# Sensors.net
KiCad netlist of a schematic drawn in Altium Designer
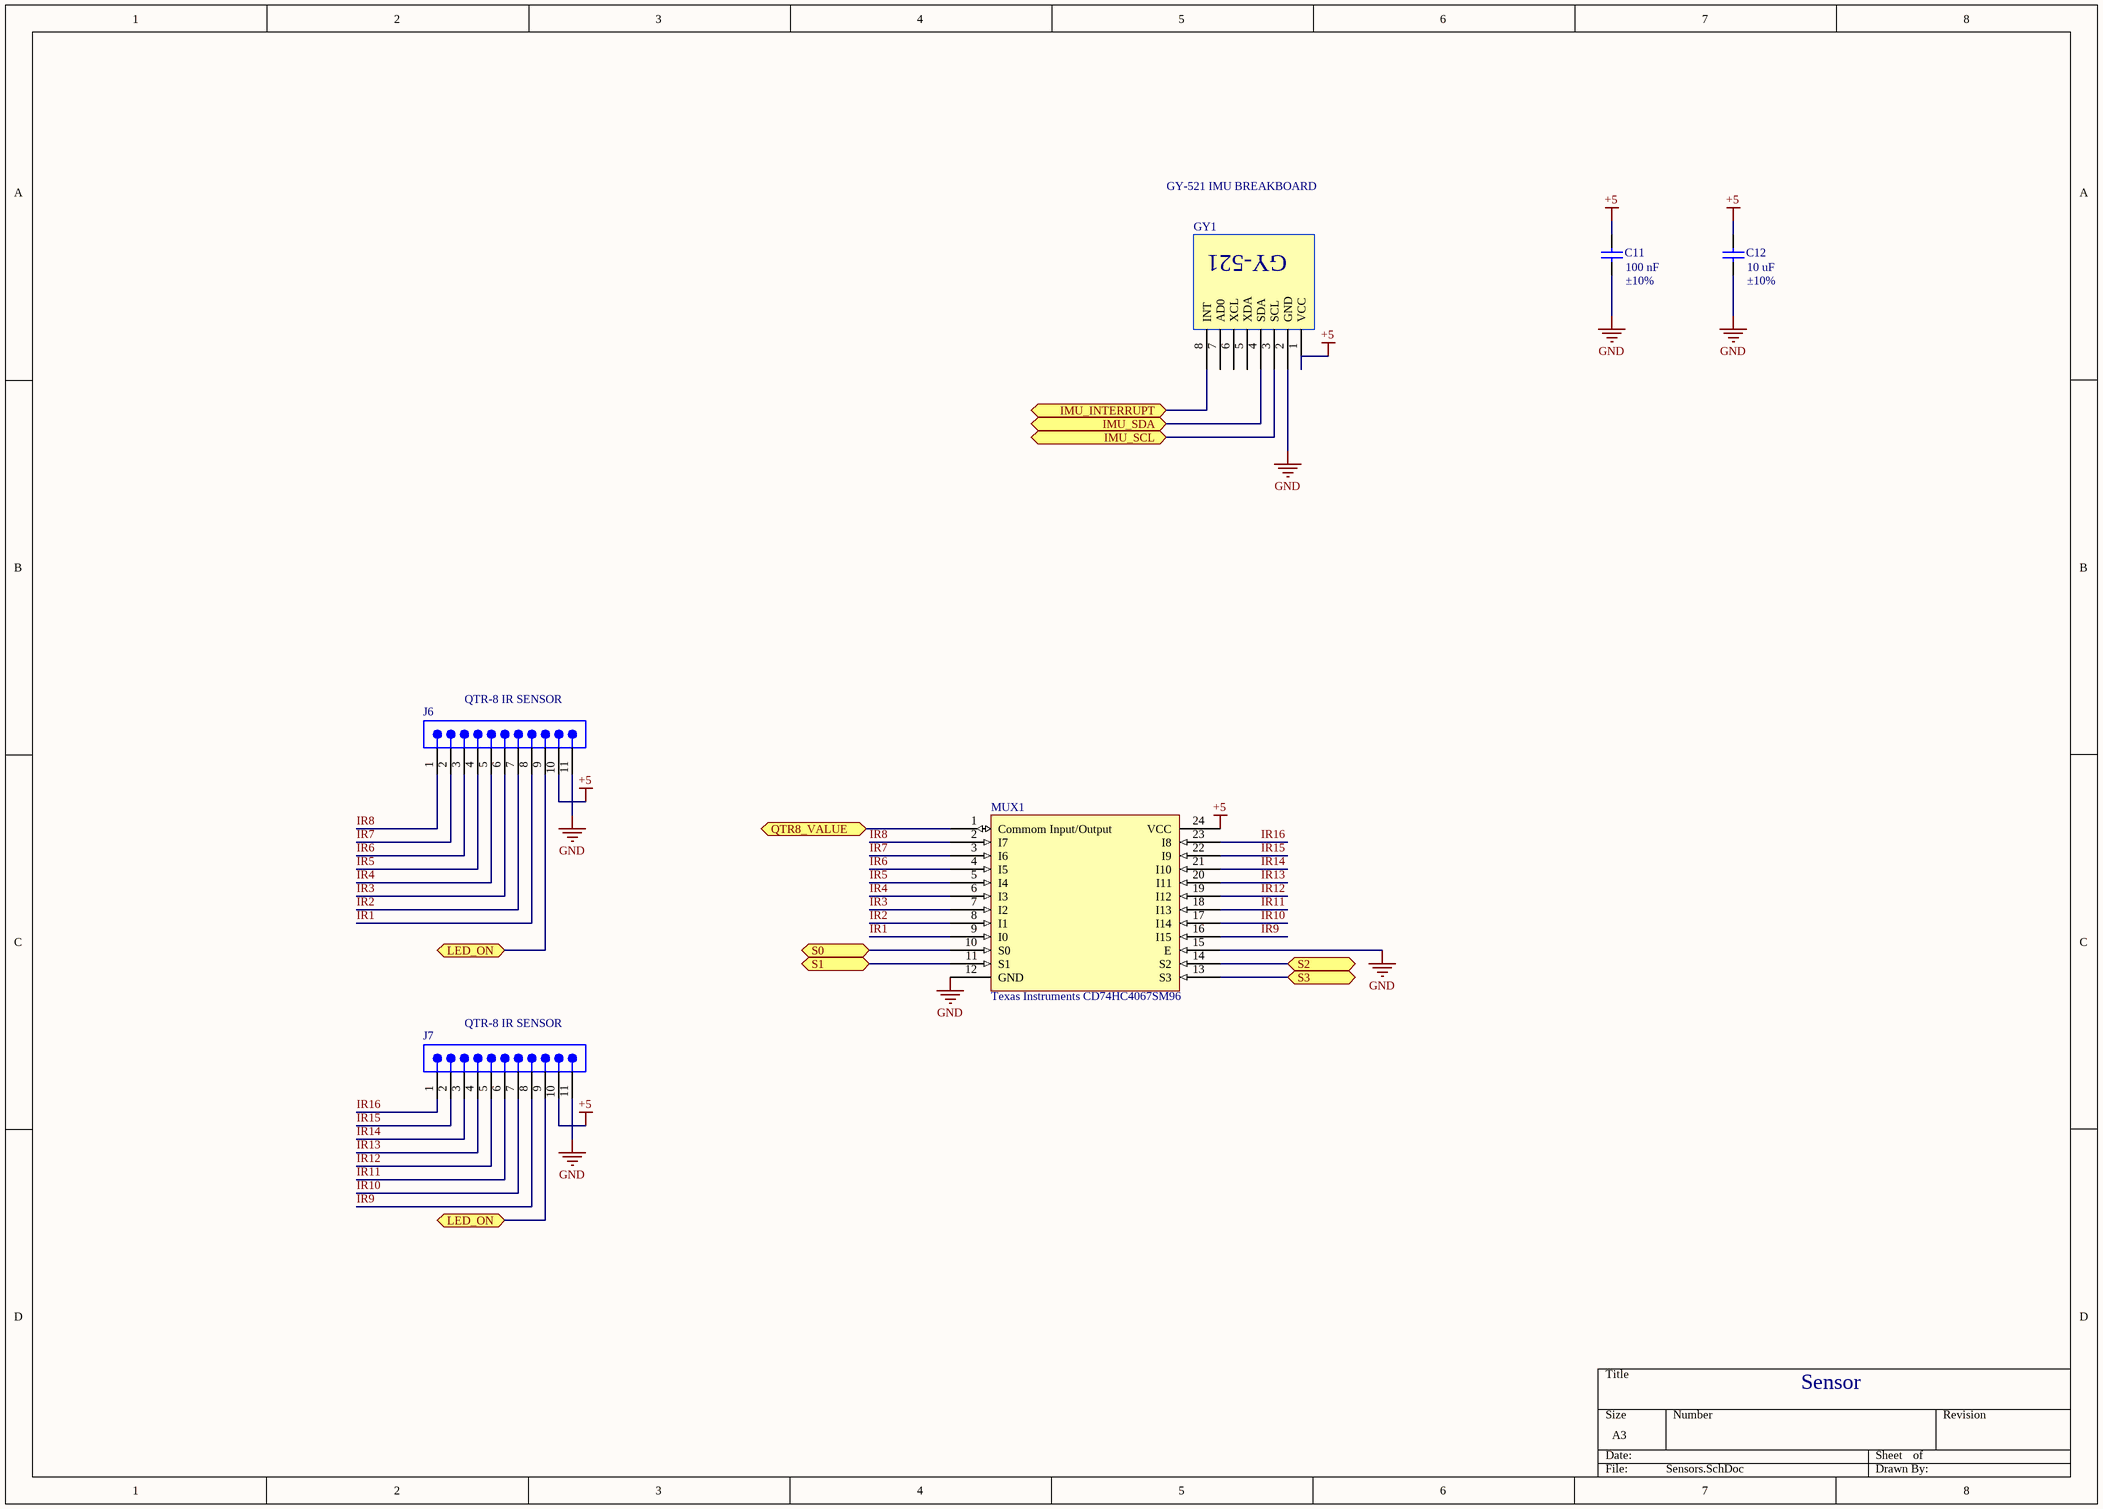
[diagram p0: Sensors.SchDoc]

(export (version "E")
  (design (tool "Eeschema 10.0.6"))
  (components
    (comp (ref "C11")
      (value "Taiyo Yuden LMK212BJ106KG-T")
      (footprint "PCB-i747o4qnz4fc2aqkwc14-1")
      (description "Cap Ceramic 10uF 10V X5R 10% SMD 0805 85?C T/R")
      (fields
        (field (name "MANUFACTURER PART NUMBER") "LMK212BJ106KG-T")
        (field (name "CAPACITANCE") "100 nF")
        (field (name "CAPACITANCE TOLERANCE") "±10%")
      )
      (libsource (lib "CommunityVault") (part "CMP-6ecba7c24c09b10c-2"))
    )
    (comp (ref "C12")
      (value "Taiyo Yuden LMK212BJ106KG-T")
      (footprint "PCB-i747o4qnz4fc2aqkwc14-1")
      (description "Cap Ceramic 10uF 10V X5R 10% SMD 0805 85?C T/R")
      (fields
        (field (name "MANUFACTURER PART NUMBER") "LMK212BJ106KG-T")
        (field (name "CAPACITANCE") "10 uF")
        (field (name "CAPACITANCE TOLERANCE") "±10%")
      )
      (libsource (lib "CommunityVault") (part "CMP-6ecba7c24c09b10c-2"))
    )
    (comp (ref "GY1")
      (value "GY-521 MPU-6050 IMU")
      (footprint "PCBComponent_1")
      (description "3-axis gyroscope, 3-axis accelerometer breakout board")
      (fields (field (name "MANUFACTURER PART NUMBER") "MPU-6050"))
      (libsource (lib "CommunityVault") (part "SYM-29a8e18bafc8f66f-1"))
    )
    (comp (ref "J6")
      (value "Samtec TSW-111-05-G-S")
      (footprint "1X11")
      (description "CONN HEADER 11POS .100\" SGL GOLD")
      (libsource (lib "CommunityVault") (part "CMP-3970764-2"))
    )
    (comp (ref "J7")
      (value "Samtec TSW-111-05-G-S")
      (footprint "1X11")
      (description "CONN HEADER 11POS .100\" SGL GOLD")
      (libsource (lib "CommunityVault") (part "CMP-3970764-2"))
    )
    (comp (ref "MUX1")
      (value "Texas Instruments CD74HC4067SM96")
      (footprint "PCBComponent_1")
      (description "High Speed CMOS 16-Channel Analog Multiplexer/Demultiplexer 24-SSOP -55 to 125")
      (fields (field (name "MANUFACTURER PART NUMBER") "CD74HC4067SM96"))
      (libsource (lib "CommunityVault") (part "CMP-106ed96303d9cfa9-2"))
    )
  )
  (nets
    (net (code "1") (name "+5") (class "Default")
      (node (ref "C11") (pin "2") (pinfunction "2_2") (pintype "passive"))
      (node (ref "C12") (pin "2") (pinfunction "2_2") (pintype "passive"))
      (node (ref "GY1") (pin "1") (pinfunction "VCC_1") (pintype "power_in"))
      (node (ref "J6") (pin "10") (pinfunction "10_10") (pintype "passive"))
      (node (ref "J7") (pin "10") (pinfunction "10_10") (pintype "passive"))
      (node (ref "MUX1") (pin "24") (pinfunction "VCC_24") (pintype "power_in"))
    )
    (net (code "2") (name "/IMU_INTERRUPT") (class "Default")
      (node (ref "GY1") (pin "8") (pinfunction "INT_8") (pintype "passive"))
    )
    (net (code "3") (name "/IMU_SCL") (class "Default")
      (node (ref "GY1") (pin "3") (pinfunction "SCL_3") (pintype "passive"))
    )
    (net (code "4") (name "/IMU_SDA") (class "Default")
      (node (ref "GY1") (pin "4") (pinfunction "SDA_4") (pintype "passive"))
    )
    (net (code "5") (name "/IR1") (class "Default")
      (node (ref "J6") (pin "8") (pinfunction "8_8") (pintype "passive"))
      (node (ref "MUX1") (pin "9") (pinfunction "I0_9") (pintype "input"))
    )
    (net (code "6") (name "/IR2") (class "Default")
      (node (ref "J6") (pin "7") (pinfunction "7_7") (pintype "passive"))
      (node (ref "MUX1") (pin "8") (pinfunction "I1_8") (pintype "input"))
    )
    (net (code "7") (name "/IR3") (class "Default")
      (node (ref "J6") (pin "6") (pinfunction "6_6") (pintype "passive"))
      (node (ref "MUX1") (pin "7") (pinfunction "I2_7") (pintype "input"))
    )
    (net (code "8") (name "/IR4") (class "Default")
      (node (ref "J6") (pin "5") (pinfunction "5_5") (pintype "passive"))
      (node (ref "MUX1") (pin "6") (pinfunction "I3_6") (pintype "input"))
    )
    (net (code "9") (name "/IR5") (class "Default")
      (node (ref "J6") (pin "4") (pinfunction "4_4") (pintype "passive"))
      (node (ref "MUX1") (pin "5") (pinfunction "I4_5") (pintype "input"))
    )
    (net (code "10") (name "/IR6") (class "Default")
      (node (ref "J6") (pin "3") (pinfunction "3_3") (pintype "passive"))
      (node (ref "MUX1") (pin "4") (pinfunction "I5_4") (pintype "input"))
    )
    (net (code "11") (name "/IR7") (class "Default")
      (node (ref "J6") (pin "2") (pinfunction "2_2") (pintype "passive"))
      (node (ref "MUX1") (pin "3") (pinfunction "I6_3") (pintype "input"))
    )
    (net (code "12") (name "/IR8") (class "Default")
      (node (ref "J6") (pin "1") (pinfunction "1_1") (pintype "passive"))
      (node (ref "MUX1") (pin "2") (pinfunction "I7_2") (pintype "input"))
    )
    (net (code "13") (name "/IR9") (class "Default")
      (node (ref "J7") (pin "8") (pinfunction "8_8") (pintype "passive"))
      (node (ref "MUX1") (pin "16") (pinfunction "I15_16") (pintype "input"))
    )
    (net (code "14") (name "/IR10") (class "Default")
      (node (ref "J7") (pin "7") (pinfunction "7_7") (pintype "passive"))
      (node (ref "MUX1") (pin "17") (pinfunction "I14_17") (pintype "input"))
    )
    (net (code "15") (name "/IR11") (class "Default")
      (node (ref "J7") (pin "6") (pinfunction "6_6") (pintype "passive"))
      (node (ref "MUX1") (pin "18") (pinfunction "I13_18") (pintype "input"))
    )
    (net (code "16") (name "/IR12") (class "Default")
      (node (ref "J7") (pin "5") (pinfunction "5_5") (pintype "passive"))
      (node (ref "MUX1") (pin "19") (pinfunction "I12_19") (pintype "input"))
    )
    (net (code "17") (name "/IR13") (class "Default")
      (node (ref "J7") (pin "4") (pinfunction "4_4") (pintype "passive"))
      (node (ref "MUX1") (pin "20") (pinfunction "I11_20") (pintype "input"))
    )
    (net (code "18") (name "/IR14") (class "Default")
      (node (ref "J7") (pin "3") (pinfunction "3_3") (pintype "passive"))
      (node (ref "MUX1") (pin "21") (pinfunction "I10_21") (pintype "input"))
    )
    (net (code "19") (name "/IR15") (class "Default")
      (node (ref "J7") (pin "2") (pinfunction "2_2") (pintype "passive"))
      (node (ref "MUX1") (pin "22") (pinfunction "I9_22") (pintype "input"))
    )
    (net (code "20") (name "/IR16") (class "Default")
      (node (ref "J7") (pin "1") (pinfunction "1_1") (pintype "passive"))
      (node (ref "MUX1") (pin "23") (pinfunction "I8_23") (pintype "input"))
    )
    (net (code "21") (name "/LED_ON") (class "Default")
      (node (ref "J6") (pin "9") (pinfunction "9_9") (pintype "passive"))
      (node (ref "J7") (pin "9") (pinfunction "9_9") (pintype "passive"))
    )
    (net (code "22") (name "/QTR8_VALUE") (class "Default")
      (node (ref "MUX1") (pin "1") (pinfunction "Commom_Input/Output_1") (pintype "bidirectional"))
    )
    (net (code "23") (name "/S0") (class "Default")
      (node (ref "MUX1") (pin "10") (pinfunction "S0_10") (pintype "input"))
    )
    (net (code "24") (name "/S1") (class "Default")
      (node (ref "MUX1") (pin "11") (pinfunction "S1_11") (pintype "input"))
    )
    (net (code "25") (name "/S2") (class "Default")
      (node (ref "MUX1") (pin "14") (pinfunction "S2_14") (pintype "input"))
    )
    (net (code "26") (name "/S3") (class "Default")
      (node (ref "MUX1") (pin "13") (pinfunction "S3_13") (pintype "input"))
    )
    (net (code "27") (name "GND") (class "Default")
      (node (ref "C11") (pin "1") (pinfunction "1_1") (pintype "passive"))
      (node (ref "C12") (pin "1") (pinfunction "1_1") (pintype "passive"))
      (node (ref "GY1") (pin "2") (pinfunction "GND_2") (pintype "power_in"))
      (node (ref "J6") (pin "11") (pinfunction "11_11") (pintype "passive"))
      (node (ref "J7") (pin "11") (pinfunction "11_11") (pintype "passive"))
      (node (ref "MUX1") (pin "12") (pinfunction "GND_12") (pintype "power_in"))
      (node (ref "MUX1") (pin "15") (pinfunction "E_15") (pintype "input"))
    )
    (net (code "28") (name "unconnected-(GY1-AD0-Pad7)") (class "Default")
      (node (ref "GY1") (pin "7") (pinfunction "AD0_7") (pintype "passive"))
    )
    (net (code "29") (name "unconnected-(GY1-XCL-Pad6)") (class "Default")
      (node (ref "GY1") (pin "6") (pinfunction "XCL_6") (pintype "passive"))
    )
    (net (code "30") (name "unconnected-(GY1-XDA-Pad5)") (class "Default")
      (node (ref "GY1") (pin "5") (pinfunction "XDA_5") (pintype "passive"))
    )
  )
)
